# TankFuzz.net
KiCad netlist of a schematic drawn in EAGLE
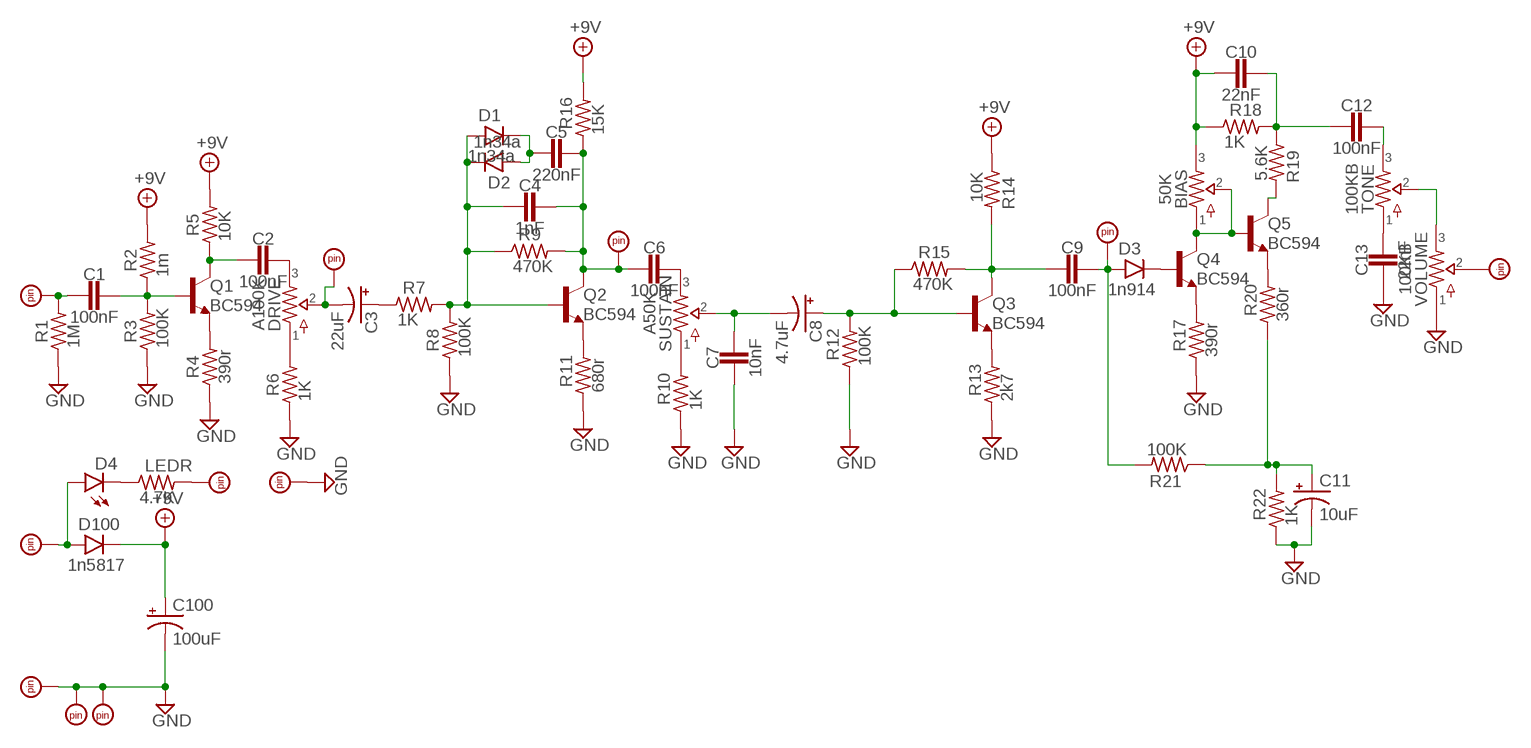
[diagram p0: schematic, sheet 1]

(export (version "E")
  (design (tool "Eeschema 10.0.6"))
  (components
    (comp (ref "BIAS")
      (value "50K")
      (footprint "eagle-import:TRIM3")
      (libsource (lib "eagle-import") (part "TRIMMERTRIM3"))
    )
    (comp (ref "C1")
      (value "100nF")
      (footprint "eagle-import:0.2_.MED")
      (libsource (lib "eagle-import") (part "CAP.3"))
    )
    (comp (ref "C2")
      (value "100nF")
      (footprint "eagle-import:0.2_.MED")
      (libsource (lib "eagle-import") (part "CAP.3"))
    )
    (comp (ref "C3")
      (value "22uF")
      (footprint "eagle-import:050_020_1")
      (libsource (lib "eagle-import") (part "0501"))
    )
    (comp (ref "C4")
      (value "1nF")
      (footprint "eagle-import:0.2_.MED")
      (libsource (lib "eagle-import") (part "CAP.3"))
    )
    (comp (ref "C5")
      (value "220nF")
      (footprint "eagle-import:0.2_.MED")
      (libsource (lib "eagle-import") (part "CAP.3"))
    )
    (comp (ref "C6")
      (value "100nF")
      (footprint "eagle-import:0.2_.MED")
      (libsource (lib "eagle-import") (part "CAP.3"))
    )
    (comp (ref "C7")
      (value "10nF")
      (footprint "eagle-import:0.2_.MED")
      (libsource (lib "eagle-import") (part "CAP.3"))
    )
    (comp (ref "C8")
      (value "4.7uF")
      (footprint "eagle-import:050_020_1")
      (libsource (lib "eagle-import") (part "0501"))
    )
    (comp (ref "C9")
      (value "100nF")
      (footprint "eagle-import:0.2_.MED")
      (libsource (lib "eagle-import") (part "CAP.3"))
    )
    (comp (ref "C10")
      (value "22nF")
      (footprint "eagle-import:0.2_.MED")
      (libsource (lib "eagle-import") (part "CAP.3"))
    )
    (comp (ref "C11")
      (value "10uF")
      (footprint "eagle-import:050_020_1")
      (libsource (lib "eagle-import") (part "0501"))
    )
    (comp (ref "C12")
      (value "100nF")
      (footprint "eagle-import:0.2_.MED")
      (libsource (lib "eagle-import") (part "CAP.3"))
    )
    (comp (ref "C13")
      (value "22nF")
      (footprint "eagle-import:0.2_.MED")
      (libsource (lib "eagle-import") (part "CAP.3"))
    )
    (comp (ref "C100")
      (value "100uF")
      (footprint "eagle-import:050_020_1")
      (libsource (lib "eagle-import") (part "0501"))
    )
    (comp (ref "D1")
      (value "1n34a")
      (footprint "eagle-import:DO35-3")
      (libsource (lib "eagle-import") (part "DO35.3"))
    )
    (comp (ref "D2")
      (value "1n34a")
      (footprint "eagle-import:DO35-3")
      (libsource (lib "eagle-import") (part "DO35.3"))
    )
    (comp (ref "D3")
      (value "1n914")
      (footprint "eagle-import:DO35-3")
      (libsource (lib "eagle-import") (part "DO35.3"))
    )
    (comp (ref "D4")
      (value "LED3MM")
      (footprint "eagle-import:LED3MM")
      (libsource (lib "eagle-import") (part "LED3MM"))
    )
    (comp (ref "D100")
      (value "1n5817")
      (footprint "eagle-import:DO41-3")
      (libsource (lib "eagle-import") (part "DO41.3"))
    )
    (comp (ref "DRIVE")
      (value "A100K")
      (footprint "eagle-import:16MM_B.MOUNT")
      (libsource (lib "eagle-import") (part "16MM.1"))
    )
    (comp (ref "LEDR")
      (value "4.7K")
      (footprint "eagle-import:R0207_3")
      (libsource (lib "eagle-import") (part "RESISTORS.3B"))
    )
    (comp (ref "Q1")
      (value "BC594")
      (footprint "eagle-import:TO92")
      (libsource (lib "eagle-import") (part "2N5088"))
    )
    (comp (ref "Q2")
      (value "BC594")
      (footprint "eagle-import:TO92")
      (libsource (lib "eagle-import") (part "2N5088"))
    )
    (comp (ref "Q3")
      (value "BC594")
      (footprint "eagle-import:TO92")
      (libsource (lib "eagle-import") (part "2N5088"))
    )
    (comp (ref "Q4")
      (value "BC594")
      (footprint "eagle-import:TO92")
      (libsource (lib "eagle-import") (part "2N5088"))
    )
    (comp (ref "Q5")
      (value "BC594")
      (footprint "eagle-import:TO92")
      (libsource (lib "eagle-import") (part "2N5088"))
    )
    (comp (ref "R1")
      (value "1M")
      (footprint "eagle-import:R0207_3")
      (libsource (lib "eagle-import") (part "RESISTORS.3B"))
    )
    (comp (ref "R2")
      (value "1m")
      (footprint "eagle-import:R0207_3")
      (libsource (lib "eagle-import") (part "RESISTORS.3B"))
    )
    (comp (ref "R3")
      (value "100K")
      (footprint "eagle-import:R0207_3")
      (libsource (lib "eagle-import") (part "RESISTORS.3B"))
    )
    (comp (ref "R4")
      (value "390r")
      (footprint "eagle-import:R0207_3")
      (libsource (lib "eagle-import") (part "RESISTORS.3B"))
    )
    (comp (ref "R5")
      (value "10K")
      (footprint "eagle-import:R0207_3")
      (libsource (lib "eagle-import") (part "RESISTORS.3B"))
    )
    (comp (ref "R6")
      (value "1K")
      (footprint "eagle-import:R0207_3")
      (libsource (lib "eagle-import") (part "RESISTORS.3B"))
    )
    (comp (ref "R7")
      (value "1K")
      (footprint "eagle-import:R0207_3")
      (libsource (lib "eagle-import") (part "RESISTORS.3B"))
    )
    (comp (ref "R8")
      (value "100K")
      (footprint "eagle-import:R0207_3")
      (libsource (lib "eagle-import") (part "RESISTORS.3B"))
    )
    (comp (ref "R9")
      (value "470K")
      (footprint "eagle-import:R0207_3")
      (libsource (lib "eagle-import") (part "RESISTORS.3B"))
    )
    (comp (ref "R10")
      (value "1K")
      (footprint "eagle-import:R0207_3")
      (libsource (lib "eagle-import") (part "RESISTORS.3B"))
    )
    (comp (ref "R11")
      (value "680r")
      (footprint "eagle-import:R0207_3")
      (libsource (lib "eagle-import") (part "RESISTORS.3B"))
    )
    (comp (ref "R12")
      (value "100K")
      (footprint "eagle-import:R0207_3")
      (libsource (lib "eagle-import") (part "RESISTORS.3B"))
    )
    (comp (ref "R13")
      (value "2k7")
      (footprint "eagle-import:R0207_3")
      (libsource (lib "eagle-import") (part "RESISTORS.3B"))
    )
    (comp (ref "R14")
      (value "10K")
      (footprint "eagle-import:R0207_3")
      (libsource (lib "eagle-import") (part "RESISTORS.3B"))
    )
    (comp (ref "R15")
      (value "470K")
      (footprint "eagle-import:R0207_3")
      (libsource (lib "eagle-import") (part "RESISTORS.3B"))
    )
    (comp (ref "R16")
      (value "15K")
      (footprint "eagle-import:R0207_3")
      (libsource (lib "eagle-import") (part "RESISTORS.3B"))
    )
    (comp (ref "R17")
      (value "390r")
      (footprint "eagle-import:R0207_3")
      (libsource (lib "eagle-import") (part "RESISTORS.3B"))
    )
    (comp (ref "R18")
      (value "1K")
      (footprint "eagle-import:R0207_3")
      (libsource (lib "eagle-import") (part "RESISTORS.3B"))
    )
    (comp (ref "R19")
      (value "5.6K")
      (footprint "eagle-import:R0207_3")
      (libsource (lib "eagle-import") (part "RESISTORS.3B"))
    )
    (comp (ref "R20")
      (value "360r")
      (footprint "eagle-import:R0207_3")
      (libsource (lib "eagle-import") (part "RESISTORS.3B"))
    )
    (comp (ref "R21")
      (value "100K")
      (footprint "eagle-import:R0207_3")
      (libsource (lib "eagle-import") (part "RESISTORS.3B"))
    )
    (comp (ref "R22")
      (value "1K")
      (footprint "eagle-import:R0207_3")
      (libsource (lib "eagle-import") (part "RESISTORS.3B"))
    )
    (comp (ref "SUSTAIN")
      (value "A50K")
      (footprint "eagle-import:16MM_B.MOUNT")
      (libsource (lib "eagle-import") (part "16MM.1"))
    )
    (comp (ref "TONE")
      (value "100KB")
      (footprint "eagle-import:16MM_B.MOUNT")
      (libsource (lib "eagle-import") (part "16MM.1"))
    )
    (comp (ref "U$1")
      (value "PADS.RND_NL")
      (footprint "eagle-import:PAD2")
      (libsource (lib "eagle-import") (part "PADS.RND_NL"))
    )
    (comp (ref "U$2")
      (value "PADS.RND_NL")
      (footprint "eagle-import:PAD2")
      (libsource (lib "eagle-import") (part "PADS.RND_NL"))
    )
    (comp (ref "U$3")
      (value "PADS.RND_NL")
      (footprint "eagle-import:PAD2")
      (libsource (lib "eagle-import") (part "PADS.RND_NL"))
    )
    (comp (ref "U$4")
      (value "PADS.RND_NL")
      (footprint "eagle-import:PAD2")
      (libsource (lib "eagle-import") (part "PADS.RND_NL"))
    )
    (comp (ref "U$5")
      (value "PADS.RND_NL")
      (footprint "eagle-import:PAD2")
      (libsource (lib "eagle-import") (part "PADS.RND_NL"))
    )
    (comp (ref "U$6")
      (value "PADS.RND_NL")
      (footprint "eagle-import:PAD2")
      (libsource (lib "eagle-import") (part "PADS.RND_NL"))
    )
    (comp (ref "U$8")
      (value "PADS.RND_NL")
      (footprint "eagle-import:PAD2")
      (libsource (lib "eagle-import") (part "PADS.RND_NL"))
    )
    (comp (ref "U$9")
      (value "PADS.RND_NL")
      (footprint "eagle-import:PAD2")
      (libsource (lib "eagle-import") (part "PADS.RND_NL"))
    )
    (comp (ref "U$10")
      (value "PADS.RND_NL")
      (footprint "eagle-import:PAD2")
      (libsource (lib "eagle-import") (part "PADS.RND_NL"))
    )
    (comp (ref "U$11")
      (value "PADS.RND_NL")
      (footprint "eagle-import:PAD2")
      (libsource (lib "eagle-import") (part "PADS.RND_NL"))
    )
    (comp (ref "U$12")
      (value "PADS.RND_NL")
      (footprint "eagle-import:PAD2")
      (libsource (lib "eagle-import") (part "PADS.RND_NL"))
    )
    (comp (ref "VOLUME")
      (value "100KB")
      (footprint "eagle-import:16MM_B.MOUNT")
      (libsource (lib "eagle-import") (part "16MM.1"))
    )
  )
  (nets
    (net (code "1") (name "+9V") (class "Default")
      (node (ref "BIAS") (pin "3") (pinfunction "3_3") (pintype "passive"))
      (node (ref "BIAS") (pin "6") (pinfunction "3_6") (pintype "passive"))
      (node (ref "C10") (pin "2") (pinfunction "2_2") (pintype "passive"))
      (node (ref "C100") (pin "+") (pinfunction "+_+") (pintype "passive"))
      (node (ref "D100") (pin "C") (pinfunction "C_C") (pintype "passive"))
      (node (ref "R14") (pin "1") (pinfunction "1_1") (pintype "passive"))
      (node (ref "R16") (pin "2") (pinfunction "2_2") (pintype "passive"))
      (node (ref "R18") (pin "1") (pinfunction "1_1") (pintype "passive"))
      (node (ref "R2") (pin "2") (pinfunction "2_2") (pintype "passive"))
      (node (ref "R5") (pin "2") (pinfunction "2_2") (pintype "passive"))
    )
    (net (code "2") (name "GND") (class "Default")
      (node (ref "C100") (pin "-") (pinfunction "-_-") (pintype "passive"))
      (node (ref "C11") (pin "-") (pinfunction "-_-") (pintype "passive"))
      (node (ref "C13") (pin "2") (pinfunction "2_2") (pintype "passive"))
      (node (ref "C7") (pin "2") (pinfunction "2_2") (pintype "passive"))
      (node (ref "R1") (pin "1") (pinfunction "1_1") (pintype "passive"))
      (node (ref "R10") (pin "1") (pinfunction "1_1") (pintype "passive"))
      (node (ref "R11") (pin "1") (pinfunction "1_1") (pintype "passive"))
      (node (ref "R12") (pin "1") (pinfunction "1_1") (pintype "passive"))
      (node (ref "R13") (pin "1") (pinfunction "1_1") (pintype "passive"))
      (node (ref "R17") (pin "1") (pinfunction "1_1") (pintype "passive"))
      (node (ref "R22") (pin "1") (pinfunction "1_1") (pintype "passive"))
      (node (ref "R3") (pin "1") (pinfunction "1_1") (pintype "passive"))
      (node (ref "R4") (pin "1") (pinfunction "1_1") (pintype "passive"))
      (node (ref "R6") (pin "1") (pinfunction "1_1") (pintype "passive"))
      (node (ref "R8") (pin "1") (pinfunction "1_1") (pintype "passive"))
      (node (ref "U$4") (pin "P$1") (pinfunction "P$1_P$1") (pintype "bidirectional"))
      (node (ref "U$6") (pin "P$1") (pinfunction "P$1_P$1") (pintype "bidirectional"))
      (node (ref "U$8") (pin "P$1") (pinfunction "P$1_P$1") (pintype "bidirectional"))
      (node (ref "U$9") (pin "P$1") (pinfunction "P$1_P$1") (pintype "bidirectional"))
      (node (ref "VOLUME") (pin "1") (pinfunction "1_1") (pintype "passive"))
    )
    (net (code "3") (name "Net-(C1-Pad2)") (class "Default")
      (node (ref "C1") (pin "2") (pinfunction "2_2") (pintype "passive"))
      (node (ref "R1") (pin "2") (pinfunction "2_2") (pintype "passive"))
      (node (ref "U$1") (pin "P$1") (pinfunction "P$1_P$1") (pintype "bidirectional"))
    )
    (net (code "4") (name "Net-(C2-Pad1)") (class "Default")
      (node (ref "C2") (pin "1") (pinfunction "1_1") (pintype "passive"))
      (node (ref "DRIVE") (pin "3") (pinfunction "3_3") (pintype "passive"))
    )
    (net (code "5") (name "Net-(C3-Pad+)") (class "Default")
      (node (ref "C3") (pin "+") (pinfunction "+_+") (pintype "passive"))
      (node (ref "R7") (pin "1") (pinfunction "1_1") (pintype "passive"))
    )
    (net (code "6") (name "Net-(C3-Pad-)") (class "Default")
      (node (ref "C3") (pin "-") (pinfunction "-_-") (pintype "passive"))
      (node (ref "DRIVE") (pin "2") (pinfunction "2_2") (pintype "passive"))
      (node (ref "U$10") (pin "P$1") (pinfunction "P$1_P$1") (pintype "bidirectional"))
    )
    (net (code "7") (name "Net-(C5-Pad2)") (class "Default")
      (node (ref "C5") (pin "2") (pinfunction "2_2") (pintype "passive"))
      (node (ref "D1") (pin "C") (pinfunction "C_C") (pintype "passive"))
      (node (ref "D2") (pin "A") (pinfunction "A_A") (pintype "passive"))
    )
    (net (code "8") (name "Net-(C6-Pad1)") (class "Default")
      (node (ref "C6") (pin "1") (pinfunction "1_1") (pintype "passive"))
      (node (ref "SUSTAIN") (pin "3") (pinfunction "3_3") (pintype "passive"))
    )
    (net (code "9") (name "Net-(C7-Pad1)") (class "Default")
      (node (ref "C7") (pin "1") (pinfunction "1_1") (pintype "passive"))
      (node (ref "C8") (pin "-") (pinfunction "-_-") (pintype "passive"))
      (node (ref "SUSTAIN") (pin "2") (pinfunction "2_2") (pintype "passive"))
    )
    (net (code "10") (name "Net-(C9-Pad1)") (class "Default")
      (node (ref "C9") (pin "1") (pinfunction "1_1") (pintype "passive"))
      (node (ref "D3") (pin "A") (pinfunction "A_A") (pintype "passive"))
      (node (ref "R21") (pin "2") (pinfunction "2_2") (pintype "passive"))
      (node (ref "U$12") (pin "P$1") (pinfunction "P$1_P$1") (pintype "bidirectional"))
    )
    (net (code "11") (name "Net-(C10-Pad1)") (class "Default")
      (node (ref "C10") (pin "1") (pinfunction "1_1") (pintype "passive"))
      (node (ref "C12") (pin "2") (pinfunction "2_2") (pintype "passive"))
      (node (ref "R18") (pin "2") (pinfunction "2_2") (pintype "passive"))
      (node (ref "R19") (pin "1") (pinfunction "1_1") (pintype "passive"))
    )
    (net (code "12") (name "Net-(C11-Pad+)") (class "Default")
      (node (ref "C11") (pin "+") (pinfunction "+_+") (pintype "passive"))
      (node (ref "R20") (pin "1") (pinfunction "1_1") (pintype "passive"))
      (node (ref "R21") (pin "1") (pinfunction "1_1") (pintype "passive"))
      (node (ref "R22") (pin "2") (pinfunction "2_2") (pintype "passive"))
    )
    (net (code "13") (name "Net-(C12-Pad1)") (class "Default")
      (node (ref "C12") (pin "1") (pinfunction "1_1") (pintype "passive"))
      (node (ref "TONE") (pin "3") (pinfunction "3_3") (pintype "passive"))
    )
    (net (code "14") (name "Net-(C13-Pad1)") (class "Default")
      (node (ref "C13") (pin "1") (pinfunction "1_1") (pintype "passive"))
      (node (ref "TONE") (pin "1") (pinfunction "1_1") (pintype "passive"))
    )
    (net (code "15") (name "Net-(D4-C)") (class "Default")
      (node (ref "D4") (pin "K") (pinfunction "C_K") (pintype "passive"))
      (node (ref "LEDR") (pin "1") (pinfunction "1_1") (pintype "passive"))
    )
    (net (code "16") (name "Net-(D100-PadA)") (class "Default")
      (node (ref "D100") (pin "A") (pinfunction "A_A") (pintype "passive"))
      (node (ref "D4") (pin "A") (pinfunction "A_A") (pintype "passive"))
      (node (ref "U$3") (pin "P$1") (pinfunction "P$1_P$1") (pintype "bidirectional"))
    )
    (net (code "17") (name "Net-(DRIVE-Pad1)") (class "Default")
      (node (ref "DRIVE") (pin "1") (pinfunction "1_1") (pintype "passive"))
      (node (ref "R6") (pin "2") (pinfunction "2_2") (pintype "passive"))
    )
    (net (code "18") (name "Net-(LEDR-Pad2)") (class "Default")
      (node (ref "LEDR") (pin "2") (pinfunction "2_2") (pintype "passive"))
      (node (ref "U$5") (pin "P$1") (pinfunction "P$1_P$1") (pintype "bidirectional"))
    )
    (net (code "19") (name "Net-(Q1-B)") (class "Default")
      (node (ref "C1") (pin "1") (pinfunction "1_1") (pintype "passive"))
      (node (ref "Q1") (pin "2") (pinfunction "B_2") (pintype "passive"))
      (node (ref "R2") (pin "1") (pinfunction "1_1") (pintype "passive"))
      (node (ref "R3") (pin "2") (pinfunction "2_2") (pintype "passive"))
    )
    (net (code "20") (name "Net-(Q1-C)") (class "Default")
      (node (ref "C2") (pin "2") (pinfunction "2_2") (pintype "passive"))
      (node (ref "Q1") (pin "1") (pinfunction "C_1") (pintype "passive"))
      (node (ref "R5") (pin "1") (pinfunction "1_1") (pintype "passive"))
    )
    (net (code "21") (name "Net-(Q1-E)") (class "Default")
      (node (ref "Q1") (pin "3") (pinfunction "E_3") (pintype "passive"))
      (node (ref "R4") (pin "2") (pinfunction "2_2") (pintype "passive"))
    )
    (net (code "22") (name "Net-(Q2-B)") (class "Default")
      (node (ref "C4") (pin "2") (pinfunction "2_2") (pintype "passive"))
      (node (ref "D1") (pin "A") (pinfunction "A_A") (pintype "passive"))
      (node (ref "D2") (pin "C") (pinfunction "C_C") (pintype "passive"))
      (node (ref "Q2") (pin "2") (pinfunction "B_2") (pintype "passive"))
      (node (ref "R7") (pin "2") (pinfunction "2_2") (pintype "passive"))
      (node (ref "R8") (pin "2") (pinfunction "2_2") (pintype "passive"))
      (node (ref "R9") (pin "1") (pinfunction "1_1") (pintype "passive"))
    )
    (net (code "23") (name "Net-(Q2-C)") (class "Default")
      (node (ref "C4") (pin "1") (pinfunction "1_1") (pintype "passive"))
      (node (ref "C5") (pin "1") (pinfunction "1_1") (pintype "passive"))
      (node (ref "C6") (pin "2") (pinfunction "2_2") (pintype "passive"))
      (node (ref "Q2") (pin "1") (pinfunction "C_1") (pintype "passive"))
      (node (ref "R16") (pin "1") (pinfunction "1_1") (pintype "passive"))
      (node (ref "R9") (pin "2") (pinfunction "2_2") (pintype "passive"))
      (node (ref "U$11") (pin "P$1") (pinfunction "P$1_P$1") (pintype "bidirectional"))
    )
    (net (code "24") (name "Net-(Q2-E)") (class "Default")
      (node (ref "Q2") (pin "3") (pinfunction "E_3") (pintype "passive"))
      (node (ref "R11") (pin "2") (pinfunction "2_2") (pintype "passive"))
    )
    (net (code "25") (name "Net-(Q3-B)") (class "Default")
      (node (ref "C8") (pin "+") (pinfunction "+_+") (pintype "passive"))
      (node (ref "Q3") (pin "2") (pinfunction "B_2") (pintype "passive"))
      (node (ref "R12") (pin "2") (pinfunction "2_2") (pintype "passive"))
      (node (ref "R15") (pin "1") (pinfunction "1_1") (pintype "passive"))
    )
    (net (code "26") (name "Net-(Q3-C)") (class "Default")
      (node (ref "C9") (pin "2") (pinfunction "2_2") (pintype "passive"))
      (node (ref "Q3") (pin "1") (pinfunction "C_1") (pintype "passive"))
      (node (ref "R14") (pin "2") (pinfunction "2_2") (pintype "passive"))
      (node (ref "R15") (pin "2") (pinfunction "2_2") (pintype "passive"))
    )
    (net (code "27") (name "Net-(Q3-E)") (class "Default")
      (node (ref "Q3") (pin "3") (pinfunction "E_3") (pintype "passive"))
      (node (ref "R13") (pin "2") (pinfunction "2_2") (pintype "passive"))
    )
    (net (code "28") (name "Net-(Q4-B)") (class "Default")
      (node (ref "D3") (pin "C") (pinfunction "C_C") (pintype "passive"))
      (node (ref "Q4") (pin "2") (pinfunction "B_2") (pintype "passive"))
    )
    (net (code "29") (name "Net-(Q4-C)") (class "Default")
      (node (ref "BIAS") (pin "1") (pinfunction "1_1") (pintype "passive"))
      (node (ref "BIAS") (pin "2") (pinfunction "2_2") (pintype "passive"))
      (node (ref "BIAS") (pin "4") (pinfunction "1_4") (pintype "passive"))
      (node (ref "BIAS") (pin "5") (pinfunction "2_5") (pintype "passive"))
      (node (ref "Q4") (pin "1") (pinfunction "C_1") (pintype "passive"))
      (node (ref "Q5") (pin "2") (pinfunction "B_2") (pintype "passive"))
    )
    (net (code "30") (name "Net-(Q4-E)") (class "Default")
      (node (ref "Q4") (pin "3") (pinfunction "E_3") (pintype "passive"))
      (node (ref "R17") (pin "2") (pinfunction "2_2") (pintype "passive"))
    )
    (net (code "31") (name "Net-(Q5-C)") (class "Default")
      (node (ref "Q5") (pin "1") (pinfunction "C_1") (pintype "passive"))
      (node (ref "R19") (pin "2") (pinfunction "2_2") (pintype "passive"))
    )
    (net (code "32") (name "Net-(Q5-E)") (class "Default")
      (node (ref "Q5") (pin "3") (pinfunction "E_3") (pintype "passive"))
      (node (ref "R20") (pin "2") (pinfunction "2_2") (pintype "passive"))
    )
    (net (code "33") (name "Net-(R10-Pad2)") (class "Default")
      (node (ref "R10") (pin "2") (pinfunction "2_2") (pintype "passive"))
      (node (ref "SUSTAIN") (pin "1") (pinfunction "1_1") (pintype "passive"))
    )
    (net (code "34") (name "Net-(TONE-Pad2)") (class "Default")
      (node (ref "TONE") (pin "2") (pinfunction "2_2") (pintype "passive"))
      (node (ref "VOLUME") (pin "3") (pinfunction "3_3") (pintype "passive"))
    )
    (net (code "35") (name "Net-(U$2-PadP$1)") (class "Default")
      (node (ref "U$2") (pin "P$1") (pinfunction "P$1_P$1") (pintype "bidirectional"))
      (node (ref "VOLUME") (pin "2") (pinfunction "2_2") (pintype "passive"))
    )
  )
)
